# switch.net
KiCad netlist of a schematic drawn in EAGLE
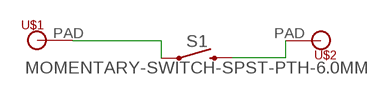
[diagram p0: schematic, sheet 1]

(export (version "E")
  (design (tool "Eeschema 10.0.6"))
  (components
    (comp (ref "S1")
      (value "MOMENTARY-SWITCH-SPST-PTH-6.0MM")
      (footprint "eagle-import:TACTILE_SWITCH_PTH_6.0MM")
      (libsource (lib "eagle-import") (part "MOMENTARY-SWITCH-SPST-PTH-6.0MM"))
    )
    (comp (ref "U$1")
      (value "pin1")
      (footprint "eagle-import:MICROBIT_PAD")
      (libsource (lib "eagle-import") (part "MICROBIT_PAD"))
    )
    (comp (ref "U$2")
      (value "MICROBIT_PAD")
      (footprint "eagle-import:MICROBIT_PAD")
      (libsource (lib "eagle-import") (part "MICROBIT_PAD"))
    )
  )
  (nets
    (net (code "1") (name "Net-(S1-2)") (class "Default")
      (node (ref "S1") (pin "3") (pinfunction "2_3") (pintype "passive"))
      (node (ref "U$2") (pin "PAD") (pinfunction "P$1_PAD") (pintype "bidirectional"))
    )
    (net (code "2") (name "Net-(U$1-P$1)") (class "Default")
      (node (ref "S1") (pin "1") (pinfunction "1_1") (pintype "passive"))
      (node (ref "U$1") (pin "PAD") (pinfunction "P$1_PAD") (pintype "bidirectional"))
    )
  )
)
